# untitled-bruecke.net
KiCad netlist of a schematic drawn in EAGLE
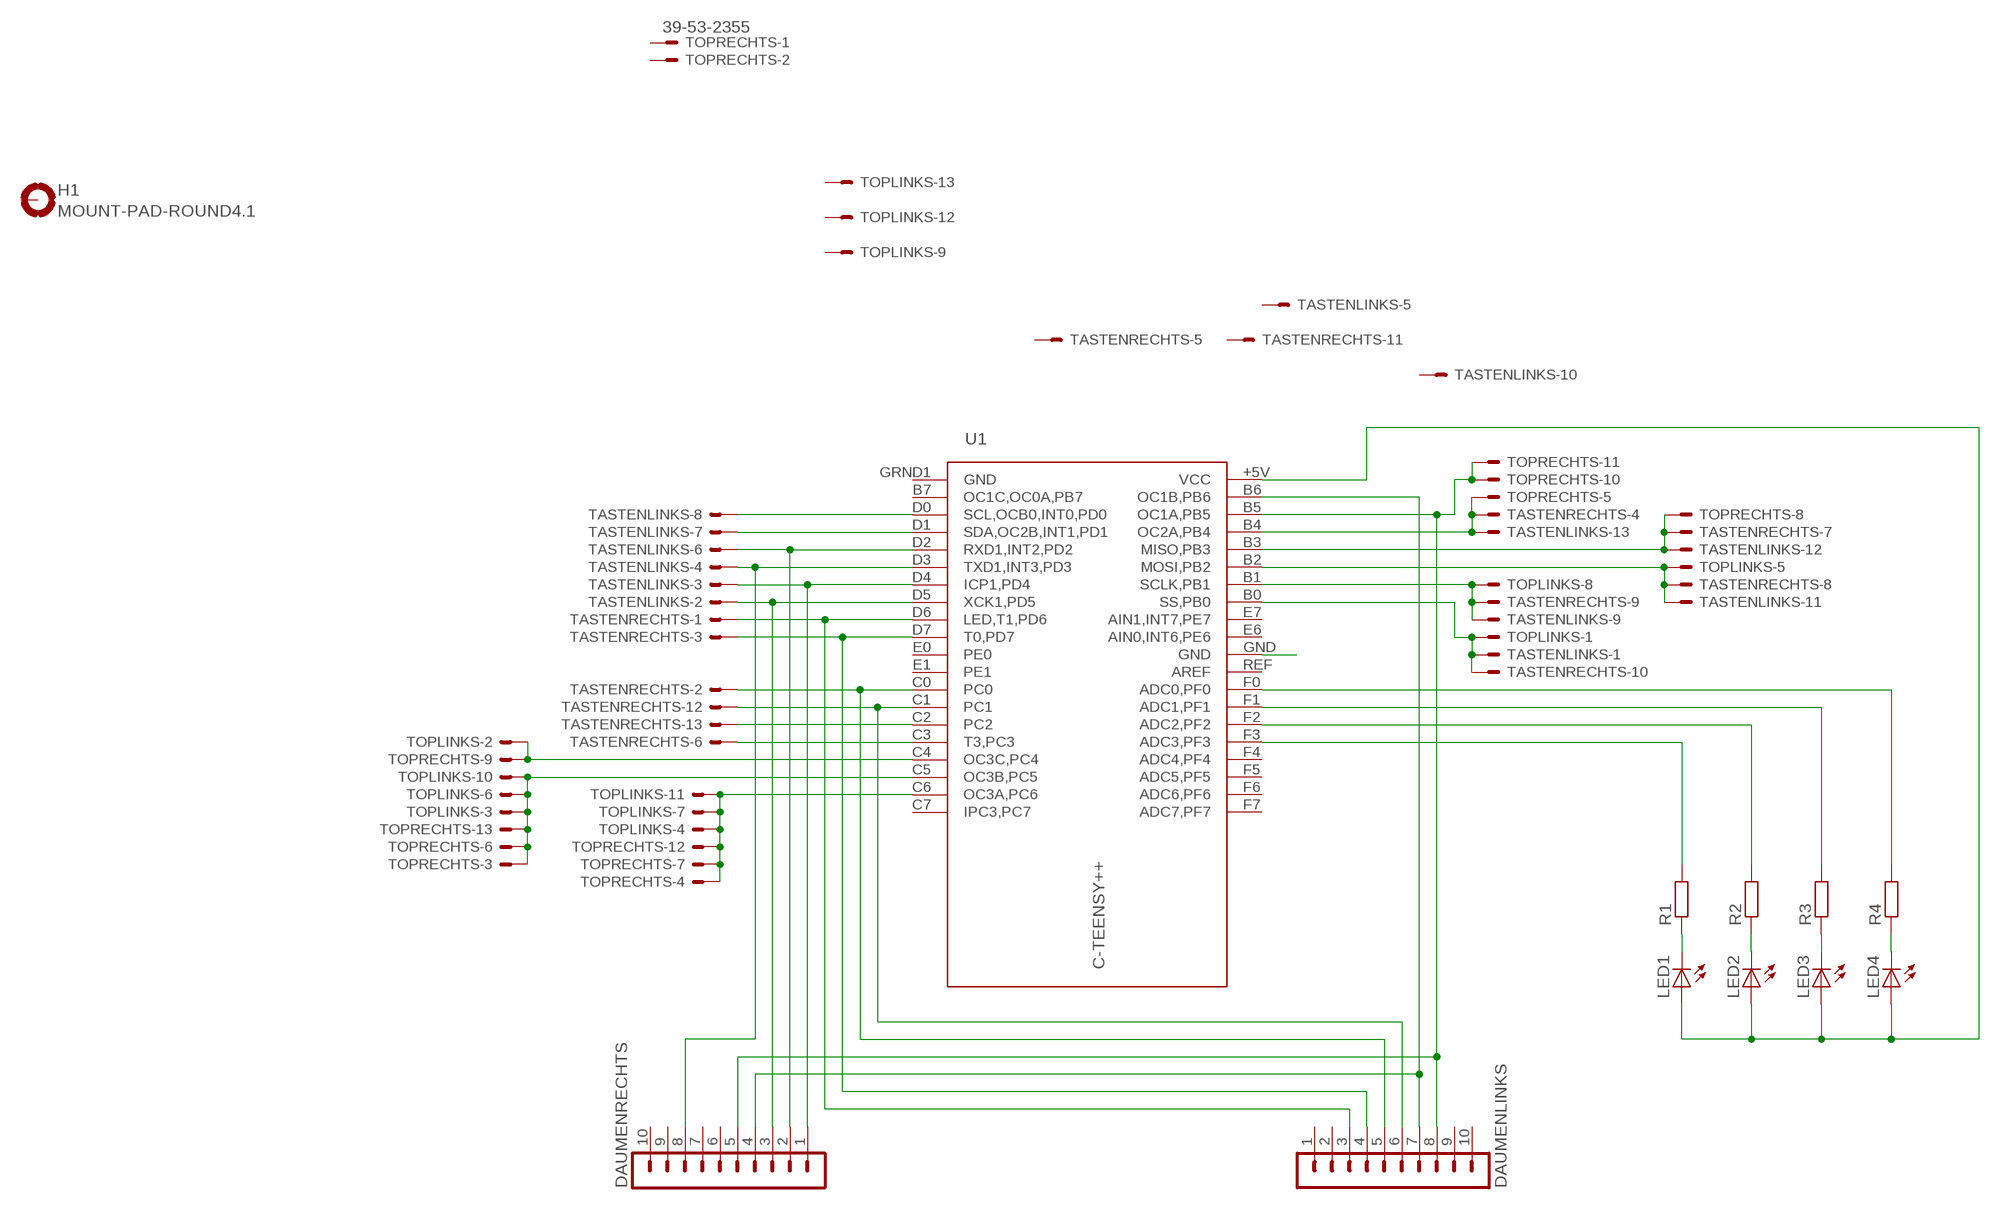
[diagram p0: schematic, sheet 1]

(export (version "E")
  (design (tool "Eeschema 10.0.6"))
  (components
    (comp (ref "DAUMENLINKS")
      (value "MA10-1")
      (footprint "eagle-import:MA10-1")
      (libsource (lib "eagle-import") (part "MA10-1"))
    )
    (comp (ref "DAUMENRECHTS")
      (value "MA10-1")
      (footprint "eagle-import:MA10-1")
      (libsource (lib "eagle-import") (part "MA10-1"))
    )
    (comp (ref "H1")
      (value "MOUNT-PAD-ROUND4.1")
      (footprint "eagle-import:4,1-PAD")
      (libsource (lib "eagle-import") (part "MOUNT-PAD-ROUND4.1"))
    )
    (comp (ref "LED1")
      (value "LED3MM")
      (footprint "eagle-import:LED3MM")
      (libsource (lib "eagle-import") (part "LED3MM"))
    )
    (comp (ref "LED2")
      (value "LED3MM")
      (footprint "eagle-import:LED3MM")
      (libsource (lib "eagle-import") (part "LED3MM"))
    )
    (comp (ref "LED3")
      (value "LED3MM")
      (footprint "eagle-import:LED3MM")
      (libsource (lib "eagle-import") (part "LED3MM"))
    )
    (comp (ref "LED4")
      (value "LED3MM")
      (footprint "eagle-import:LED3MM")
      (libsource (lib "eagle-import") (part "LED3MM"))
    )
    (comp (ref "R1")
      (value "R-EU_R1206")
      (footprint "eagle-import:R1206")
      (libsource (lib "eagle-import") (part "R-EU_R1206"))
    )
    (comp (ref "R2")
      (value "R-EU_R1206")
      (footprint "eagle-import:R1206")
      (libsource (lib "eagle-import") (part "R-EU_R1206"))
    )
    (comp (ref "R3")
      (value "R-EU_R1206")
      (footprint "eagle-import:R1206")
      (libsource (lib "eagle-import") (part "R-EU_R1206"))
    )
    (comp (ref "R4")
      (value "R-EU_R1206")
      (footprint "eagle-import:R1206")
      (libsource (lib "eagle-import") (part "R-EU_R1206"))
    )
    (comp (ref "TASTENLINKS")
      (value "39-53-2355")
      (footprint "eagle-import:39-53-2135")
      (libsource (lib "eagle-import") (part "39-53-2355"))
    )
    (comp (ref "TASTENRECHTS")
      (value "39-53-2355")
      (footprint "eagle-import:39-53-2135")
      (libsource (lib "eagle-import") (part "39-53-2355"))
    )
    (comp (ref "TOPLINKS")
      (value "39-53-2355")
      (footprint "eagle-import:39-53-2135")
      (libsource (lib "eagle-import") (part "39-53-2355"))
    )
    (comp (ref "TOPRECHTS")
      (value "39-53-2355")
      (footprint "eagle-import:39-53-2135")
      (libsource (lib "eagle-import") (part "39-53-2355"))
    )
    (comp (ref "U1")
      (value "C-TEENSY++")
      (footprint "eagle-import:TEENSY++")
      (libsource (lib "eagle-import") (part "C-TEENSY++"))
    )
  )
  (nets
    (net (code "1") (name "/GND") (class "Default")
      (node (ref "U1") (pin "GRND1") (pinfunction "GND_GRND1") (pintype "power_in"))
    )
    (net (code "2") (name "Net-(LED1-C)") (class "Default")
      (node (ref "LED1") (pin "K") (pinfunction "C_K") (pintype "passive"))
      (node (ref "R1") (pin "1") (pinfunction "1_1") (pintype "passive"))
    )
    (net (code "3") (name "Net-(LED2-C)") (class "Default")
      (node (ref "LED2") (pin "K") (pinfunction "C_K") (pintype "passive"))
      (node (ref "R2") (pin "1") (pinfunction "1_1") (pintype "passive"))
    )
    (net (code "4") (name "Net-(LED3-C)") (class "Default")
      (node (ref "LED3") (pin "K") (pinfunction "C_K") (pintype "passive"))
      (node (ref "R3") (pin "1") (pinfunction "1_1") (pintype "passive"))
    )
    (net (code "5") (name "Net-(LED4-C)") (class "Default")
      (node (ref "LED4") (pin "K") (pinfunction "C_K") (pintype "passive"))
      (node (ref "R4") (pin "1") (pinfunction "1_1") (pintype "passive"))
    )
    (net (code "6") (name "Net-(TASTENLINKSA-S)") (class "Default")
      (node (ref "TASTENLINKS") (pin "P$1") (pinfunction "S_P$1") (pintype "passive"))
      (node (ref "TASTENRECHTS") (pin "P$10") (pinfunction "S_P$10") (pintype "passive"))
      (node (ref "TOPLINKS") (pin "P$1") (pinfunction "S_P$1") (pintype "passive"))
      (node (ref "U1") (pin "B0") (pinfunction "SS,PB0_B0") (pintype "bidirectional"))
    )
    (net (code "7") (name "Net-(TASTENLINKSC-S)") (class "Default")
      (node (ref "TASTENLINKS") (pin "P$11") (pinfunction "S_P$11") (pintype "passive"))
      (node (ref "TASTENRECHTS") (pin "P$8") (pinfunction "S_P$8") (pintype "passive"))
      (node (ref "TOPLINKS") (pin "P$5") (pinfunction "S_P$5") (pintype "passive"))
      (node (ref "U1") (pin "B2") (pinfunction "MOSI,PB2_B2") (pintype "bidirectional"))
    )
    (net (code "8") (name "Net-(TASTENLINKSD-S)") (class "Default")
      (node (ref "TASTENLINKS") (pin "P$12") (pinfunction "S_P$12") (pintype "passive"))
      (node (ref "TASTENRECHTS") (pin "P$7") (pinfunction "S_P$7") (pintype "passive"))
      (node (ref "TOPRECHTS") (pin "P$8") (pinfunction "S_P$8") (pintype "passive"))
      (node (ref "U1") (pin "B3") (pinfunction "MISO,PB3_B3") (pintype "bidirectional"))
    )
    (net (code "9") (name "Net-(TASTENLINKSE-S)") (class "Default")
      (node (ref "TASTENLINKS") (pin "P$13") (pinfunction "S_P$13") (pintype "passive"))
      (node (ref "TASTENRECHTS") (pin "P$4") (pinfunction "S_P$4") (pintype "passive"))
      (node (ref "TOPRECHTS") (pin "P$5") (pinfunction "S_P$5") (pintype "passive"))
      (node (ref "U1") (pin "B4") (pinfunction "OC2A,PB4_B4") (pintype "bidirectional"))
    )
    (net (code "10") (name "Net-(TASTENLINKSF-S)") (class "Default")
      (node (ref "DAUMENRECHTS") (pin "3") (pinfunction "3_3") (pintype "passive"))
      (node (ref "TASTENLINKS") (pin "P$2") (pinfunction "S_P$2") (pintype "passive"))
      (node (ref "U1") (pin "D5") (pinfunction "XCK1,PD5_D5") (pintype "bidirectional"))
    )
    (net (code "11") (name "Net-(TASTENLINKSG-S)") (class "Default")
      (node (ref "DAUMENRECHTS") (pin "1") (pinfunction "1_1") (pintype "passive"))
      (node (ref "TASTENLINKS") (pin "P$3") (pinfunction "S_P$3") (pintype "passive"))
      (node (ref "U1") (pin "D4") (pinfunction "ICP1,PD4_D4") (pintype "bidirectional"))
    )
    (net (code "12") (name "Net-(TASTENLINKSH-S)") (class "Default")
      (node (ref "DAUMENRECHTS") (pin "8") (pinfunction "8_8") (pintype "passive"))
      (node (ref "TASTENLINKS") (pin "P$4") (pinfunction "S_P$4") (pintype "passive"))
      (node (ref "U1") (pin "D3") (pinfunction "TXD1,INT3,PD3_D3") (pintype "bidirectional"))
    )
    (net (code "13") (name "Net-(TASTENLINKSJ-S)") (class "Default")
      (node (ref "DAUMENRECHTS") (pin "2") (pinfunction "2_2") (pintype "passive"))
      (node (ref "TASTENLINKS") (pin "P$6") (pinfunction "S_P$6") (pintype "passive"))
      (node (ref "U1") (pin "D2") (pinfunction "RXD1,INT2,PD2_D2") (pintype "bidirectional"))
    )
    (net (code "14") (name "Net-(TASTENLINKSK-S)") (class "Default")
      (node (ref "TASTENLINKS") (pin "P$7") (pinfunction "S_P$7") (pintype "passive"))
      (node (ref "U1") (pin "D1") (pinfunction "SDA,OC2B,INT1,PD1_D1") (pintype "bidirectional"))
    )
    (net (code "15") (name "Net-(TASTENLINKSL-S)") (class "Default")
      (node (ref "TASTENLINKS") (pin "P$8") (pinfunction "S_P$8") (pintype "passive"))
      (node (ref "U1") (pin "D0") (pinfunction "SCL,OCB0,INT0,PD0_D0") (pintype "bidirectional"))
    )
    (net (code "16") (name "Net-(TASTENLINKSM-S)") (class "Default")
      (node (ref "TASTENLINKS") (pin "P$9") (pinfunction "S_P$9") (pintype "passive"))
      (node (ref "TASTENRECHTS") (pin "P$9") (pinfunction "S_P$9") (pintype "passive"))
      (node (ref "TOPLINKS") (pin "P$8") (pinfunction "S_P$8") (pintype "passive"))
      (node (ref "U1") (pin "B1") (pinfunction "SCLK,PB1_B1") (pintype "bidirectional"))
    )
    (net (code "17") (name "Net-(TASTENRECHTSA-S)") (class "Default")
      (node (ref "DAUMENLINKS") (pin "3") (pinfunction "3_3") (pintype "passive"))
      (node (ref "TASTENRECHTS") (pin "P$1") (pinfunction "S_P$1") (pintype "passive"))
      (node (ref "U1") (pin "D6") (pinfunction "LED,T1,PD6_D6") (pintype "bidirectional"))
    )
    (net (code "18") (name "Net-(TASTENRECHTSD-S)") (class "Default")
      (node (ref "DAUMENLINKS") (pin "6") (pinfunction "6_6") (pintype "passive"))
      (node (ref "TASTENRECHTS") (pin "P$12") (pinfunction "S_P$12") (pintype "passive"))
      (node (ref "U1") (pin "C1") (pinfunction "PC1_C1") (pintype "bidirectional"))
    )
    (net (code "19") (name "Net-(TASTENRECHTSE-S)") (class "Default")
      (node (ref "TASTENRECHTS") (pin "P$13") (pinfunction "S_P$13") (pintype "passive"))
      (node (ref "U1") (pin "C2") (pinfunction "PC2_C2") (pintype "bidirectional"))
    )
    (net (code "20") (name "Net-(TASTENRECHTSF-S)") (class "Default")
      (node (ref "DAUMENLINKS") (pin "5") (pinfunction "5_5") (pintype "passive"))
      (node (ref "TASTENRECHTS") (pin "P$2") (pinfunction "S_P$2") (pintype "passive"))
      (node (ref "U1") (pin "C0") (pinfunction "PC0_C0") (pintype "bidirectional"))
    )
    (net (code "21") (name "Net-(TASTENRECHTSG-S)") (class "Default")
      (node (ref "DAUMENLINKS") (pin "4") (pinfunction "4_4") (pintype "passive"))
      (node (ref "TASTENRECHTS") (pin "P$3") (pinfunction "S_P$3") (pintype "passive"))
      (node (ref "U1") (pin "D7") (pinfunction "T0,PD7_D7") (pintype "bidirectional"))
    )
    (net (code "22") (name "Net-(TASTENRECHTSJ-S)") (class "Default")
      (node (ref "TASTENRECHTS") (pin "P$6") (pinfunction "S_P$6") (pintype "passive"))
      (node (ref "U1") (pin "C3") (pinfunction "T3,PC3_C3") (pintype "bidirectional"))
    )
    (net (code "23") (name "Net-(TOPLINKSB-S)") (class "Default")
      (node (ref "TOPLINKS") (pin "P$10") (pinfunction "S_P$10") (pintype "passive"))
      (node (ref "TOPLINKS") (pin "P$3") (pinfunction "S_P$3") (pintype "passive"))
      (node (ref "TOPLINKS") (pin "P$6") (pinfunction "S_P$6") (pintype "passive"))
      (node (ref "TOPRECHTS") (pin "P$13") (pinfunction "S_P$13") (pintype "passive"))
      (node (ref "TOPRECHTS") (pin "P$3") (pinfunction "S_P$3") (pintype "passive"))
      (node (ref "TOPRECHTS") (pin "P$6") (pinfunction "S_P$6") (pintype "passive"))
      (node (ref "U1") (pin "C5") (pinfunction "OC3B,PC5_C5") (pintype "bidirectional"))
    )
    (net (code "24") (name "Net-(TOPLINKSC-S)") (class "Default")
      (node (ref "TOPLINKS") (pin "P$11") (pinfunction "S_P$11") (pintype "passive"))
      (node (ref "TOPLINKS") (pin "P$4") (pinfunction "S_P$4") (pintype "passive"))
      (node (ref "TOPLINKS") (pin "P$7") (pinfunction "S_P$7") (pintype "passive"))
      (node (ref "TOPRECHTS") (pin "P$12") (pinfunction "S_P$12") (pintype "passive"))
      (node (ref "TOPRECHTS") (pin "P$4") (pinfunction "S_P$4") (pintype "passive"))
      (node (ref "TOPRECHTS") (pin "P$7") (pinfunction "S_P$7") (pintype "passive"))
      (node (ref "U1") (pin "C6") (pinfunction "OC3A,PC6_C6") (pintype "bidirectional"))
    )
    (net (code "25") (name "Net-(TOPLINKSF-S)") (class "Default")
      (node (ref "TOPLINKS") (pin "P$2") (pinfunction "S_P$2") (pintype "passive"))
      (node (ref "TOPRECHTS") (pin "P$9") (pinfunction "S_P$9") (pintype "passive"))
      (node (ref "U1") (pin "C4") (pinfunction "OC3C,PC4_C4") (pintype "bidirectional"))
    )
    (net (code "26") (name "Net-(TOPRECHTSB-S)") (class "Default")
      (node (ref "DAUMENLINKS") (pin "8") (pinfunction "8_8") (pintype "passive"))
      (node (ref "DAUMENRECHTS") (pin "5") (pinfunction "5_5") (pintype "passive"))
      (node (ref "TOPRECHTS") (pin "P$10") (pinfunction "S_P$10") (pintype "passive"))
      (node (ref "TOPRECHTS") (pin "P$11") (pinfunction "S_P$11") (pintype "passive"))
      (node (ref "U1") (pin "B5") (pinfunction "OC1A,PB5_B5") (pintype "bidirectional"))
    )
    (net (code "27") (name "Net-(U1-ADC0,PF0)") (class "Default")
      (node (ref "R4") (pin "2") (pinfunction "2_2") (pintype "passive"))
      (node (ref "U1") (pin "F0") (pinfunction "ADC0,PF0_F0") (pintype "bidirectional"))
    )
    (net (code "28") (name "Net-(U1-ADC1,PF1)") (class "Default")
      (node (ref "R3") (pin "2") (pinfunction "2_2") (pintype "passive"))
      (node (ref "U1") (pin "F1") (pinfunction "ADC1,PF1_F1") (pintype "bidirectional"))
    )
    (net (code "29") (name "Net-(U1-ADC2,PF2)") (class "Default")
      (node (ref "R2") (pin "2") (pinfunction "2_2") (pintype "passive"))
      (node (ref "U1") (pin "F2") (pinfunction "ADC2,PF2_F2") (pintype "bidirectional"))
    )
    (net (code "30") (name "Net-(U1-ADC3,PF3)") (class "Default")
      (node (ref "R1") (pin "2") (pinfunction "2_2") (pintype "passive"))
      (node (ref "U1") (pin "F3") (pinfunction "ADC3,PF3_F3") (pintype "bidirectional"))
    )
    (net (code "31") (name "Net-(U1-OC1B,PB6)") (class "Default")
      (node (ref "DAUMENLINKS") (pin "7") (pinfunction "7_7") (pintype "passive"))
      (node (ref "DAUMENRECHTS") (pin "4") (pinfunction "4_4") (pintype "passive"))
      (node (ref "U1") (pin "B6") (pinfunction "OC1B,PB6_B6") (pintype "bidirectional"))
    )
    (net (code "32") (name "Net-(U1-VCC)") (class "Default")
      (node (ref "LED1") (pin "A") (pinfunction "A_A") (pintype "passive"))
      (node (ref "LED2") (pin "A") (pinfunction "A_A") (pintype "passive"))
      (node (ref "LED3") (pin "A") (pinfunction "A_A") (pintype "passive"))
      (node (ref "LED4") (pin "A") (pinfunction "A_A") (pintype "passive"))
      (node (ref "U1") (pin "+5V") (pinfunction "VCC_+5V") (pintype "power_in"))
    )
    (net (code "33") (name "unconnected-(DAUMENLINKS-Pad1)") (class "Default")
      (node (ref "DAUMENLINKS") (pin "1") (pinfunction "1_1") (pintype "passive"))
    )
    (net (code "34") (name "unconnected-(DAUMENLINKS-Pad2)") (class "Default")
      (node (ref "DAUMENLINKS") (pin "2") (pinfunction "2_2") (pintype "passive"))
    )
    (net (code "35") (name "unconnected-(DAUMENLINKS-Pad9)") (class "Default")
      (node (ref "DAUMENLINKS") (pin "9") (pinfunction "9_9") (pintype "passive"))
    )
    (net (code "36") (name "unconnected-(DAUMENLINKS-Pad10)") (class "Default")
      (node (ref "DAUMENLINKS") (pin "10") (pinfunction "10_10") (pintype "passive"))
    )
    (net (code "37") (name "unconnected-(DAUMENRECHTS-Pad6)") (class "Default")
      (node (ref "DAUMENRECHTS") (pin "6") (pinfunction "6_6") (pintype "passive"))
    )
    (net (code "38") (name "unconnected-(DAUMENRECHTS-Pad7)") (class "Default")
      (node (ref "DAUMENRECHTS") (pin "7") (pinfunction "7_7") (pintype "passive"))
    )
    (net (code "39") (name "unconnected-(DAUMENRECHTS-Pad9)") (class "Default")
      (node (ref "DAUMENRECHTS") (pin "9") (pinfunction "9_9") (pintype "passive"))
    )
    (net (code "40") (name "unconnected-(DAUMENRECHTS-Pad10)") (class "Default")
      (node (ref "DAUMENRECHTS") (pin "10") (pinfunction "10_10") (pintype "passive"))
    )
    (net (code "41") (name "unconnected-(H1-MOUNT-PadB4,1)") (class "Default")
      (node (ref "H1") (pin "B4,1") (pinfunction "MOUNT_B4,1") (pintype "passive"))
    )
    (net (code "42") (name "unconnected-(TASTENLINKSB-S-PadP$10)") (class "Default")
      (node (ref "TASTENLINKS") (pin "P$10") (pinfunction "S_P$10") (pintype "passive"))
    )
    (net (code "43") (name "unconnected-(TASTENLINKSI-S-PadP$5)") (class "Default")
      (node (ref "TASTENLINKS") (pin "P$5") (pinfunction "S_P$5") (pintype "passive"))
    )
    (net (code "44") (name "unconnected-(TASTENRECHTSC-S-PadP$11)") (class "Default")
      (node (ref "TASTENRECHTS") (pin "P$11") (pinfunction "S_P$11") (pintype "passive"))
    )
    (net (code "45") (name "unconnected-(TASTENRECHTSI-S-PadP$5)") (class "Default")
      (node (ref "TASTENRECHTS") (pin "P$5") (pinfunction "S_P$5") (pintype "passive"))
    )
    (net (code "46") (name "unconnected-(TOPLINKSD-S-PadP$12)") (class "Default")
      (node (ref "TOPLINKS") (pin "P$12") (pinfunction "S_P$12") (pintype "passive"))
    )
    (net (code "47") (name "unconnected-(TOPLINKSE-S-PadP$13)") (class "Default")
      (node (ref "TOPLINKS") (pin "P$13") (pinfunction "S_P$13") (pintype "passive"))
    )
    (net (code "48") (name "unconnected-(TOPLINKSM-S-PadP$9)") (class "Default")
      (node (ref "TOPLINKS") (pin "P$9") (pinfunction "S_P$9") (pintype "passive"))
    )
    (net (code "49") (name "unconnected-(TOPRECHTSA-S-PadP$1)") (class "Default")
      (node (ref "TOPRECHTS") (pin "P$1") (pinfunction "S_P$1") (pintype "passive"))
    )
    (net (code "50") (name "unconnected-(TOPRECHTSF-S-PadP$2)") (class "Default")
      (node (ref "TOPRECHTS") (pin "P$2") (pinfunction "S_P$2") (pintype "passive"))
    )
    (net (code "51") (name "unconnected-(U1-ADC4,PF4-PadF4)") (class "Default")
      (node (ref "U1") (pin "F4") (pinfunction "ADC4,PF4_F4") (pintype "bidirectional"))
    )
    (net (code "52") (name "unconnected-(U1-ADC5,PF5-PadF5)") (class "Default")
      (node (ref "U1") (pin "F5") (pinfunction "ADC5,PF5_F5") (pintype "bidirectional"))
    )
    (net (code "53") (name "unconnected-(U1-ADC6,PF6-PadF6)") (class "Default")
      (node (ref "U1") (pin "F6") (pinfunction "ADC6,PF6_F6") (pintype "bidirectional"))
    )
    (net (code "54") (name "unconnected-(U1-ADC7,PF7-PadF7)") (class "Default")
      (node (ref "U1") (pin "F7") (pinfunction "ADC7,PF7_F7") (pintype "bidirectional"))
    )
    (net (code "55") (name "unconnected-(U1-AIN0,INT6,PE6-PadE6)") (class "Default")
      (node (ref "U1") (pin "E6") (pinfunction "AIN0,INT6,PE6_E6") (pintype "bidirectional"))
    )
    (net (code "56") (name "unconnected-(U1-AIN1,INT7,PE7-PadE7)") (class "Default")
      (node (ref "U1") (pin "E7") (pinfunction "AIN1,INT7,PE7_E7") (pintype "bidirectional"))
    )
    (net (code "57") (name "unconnected-(U1-AREF-PadREF)") (class "Default")
      (node (ref "U1") (pin "REF") (pinfunction "AREF_REF") (pintype "input"))
    )
    (net (code "58") (name "unconnected-(U1-IPC3,PC7-PadC7)") (class "Default")
      (node (ref "U1") (pin "C7") (pinfunction "IPC3,PC7_C7") (pintype "bidirectional"))
    )
    (net (code "59") (name "unconnected-(U1-OC1C,OC0A,PB7-PadB7)") (class "Default")
      (node (ref "U1") (pin "B7") (pinfunction "OC1C,OC0A,PB7_B7") (pintype "bidirectional"))
    )
    (net (code "60") (name "unconnected-(U1-PE0-PadE0)") (class "Default")
      (node (ref "U1") (pin "E0") (pinfunction "PE0_E0") (pintype "bidirectional"))
    )
    (net (code "61") (name "unconnected-(U1-PE1-PadE1)") (class "Default")
      (node (ref "U1") (pin "E1") (pinfunction "PE1_E1") (pintype "bidirectional"))
    )
    (net (code "62") (name "unconnected-(U1-PadGND)") (class "Default")
      (node (ref "U1") (pin "GND") (pinfunction "GND_GND") (pintype "power_in"))
    )
  )
)
